# version_1.net
KiCad netlist of a schematic drawn in EAGLE
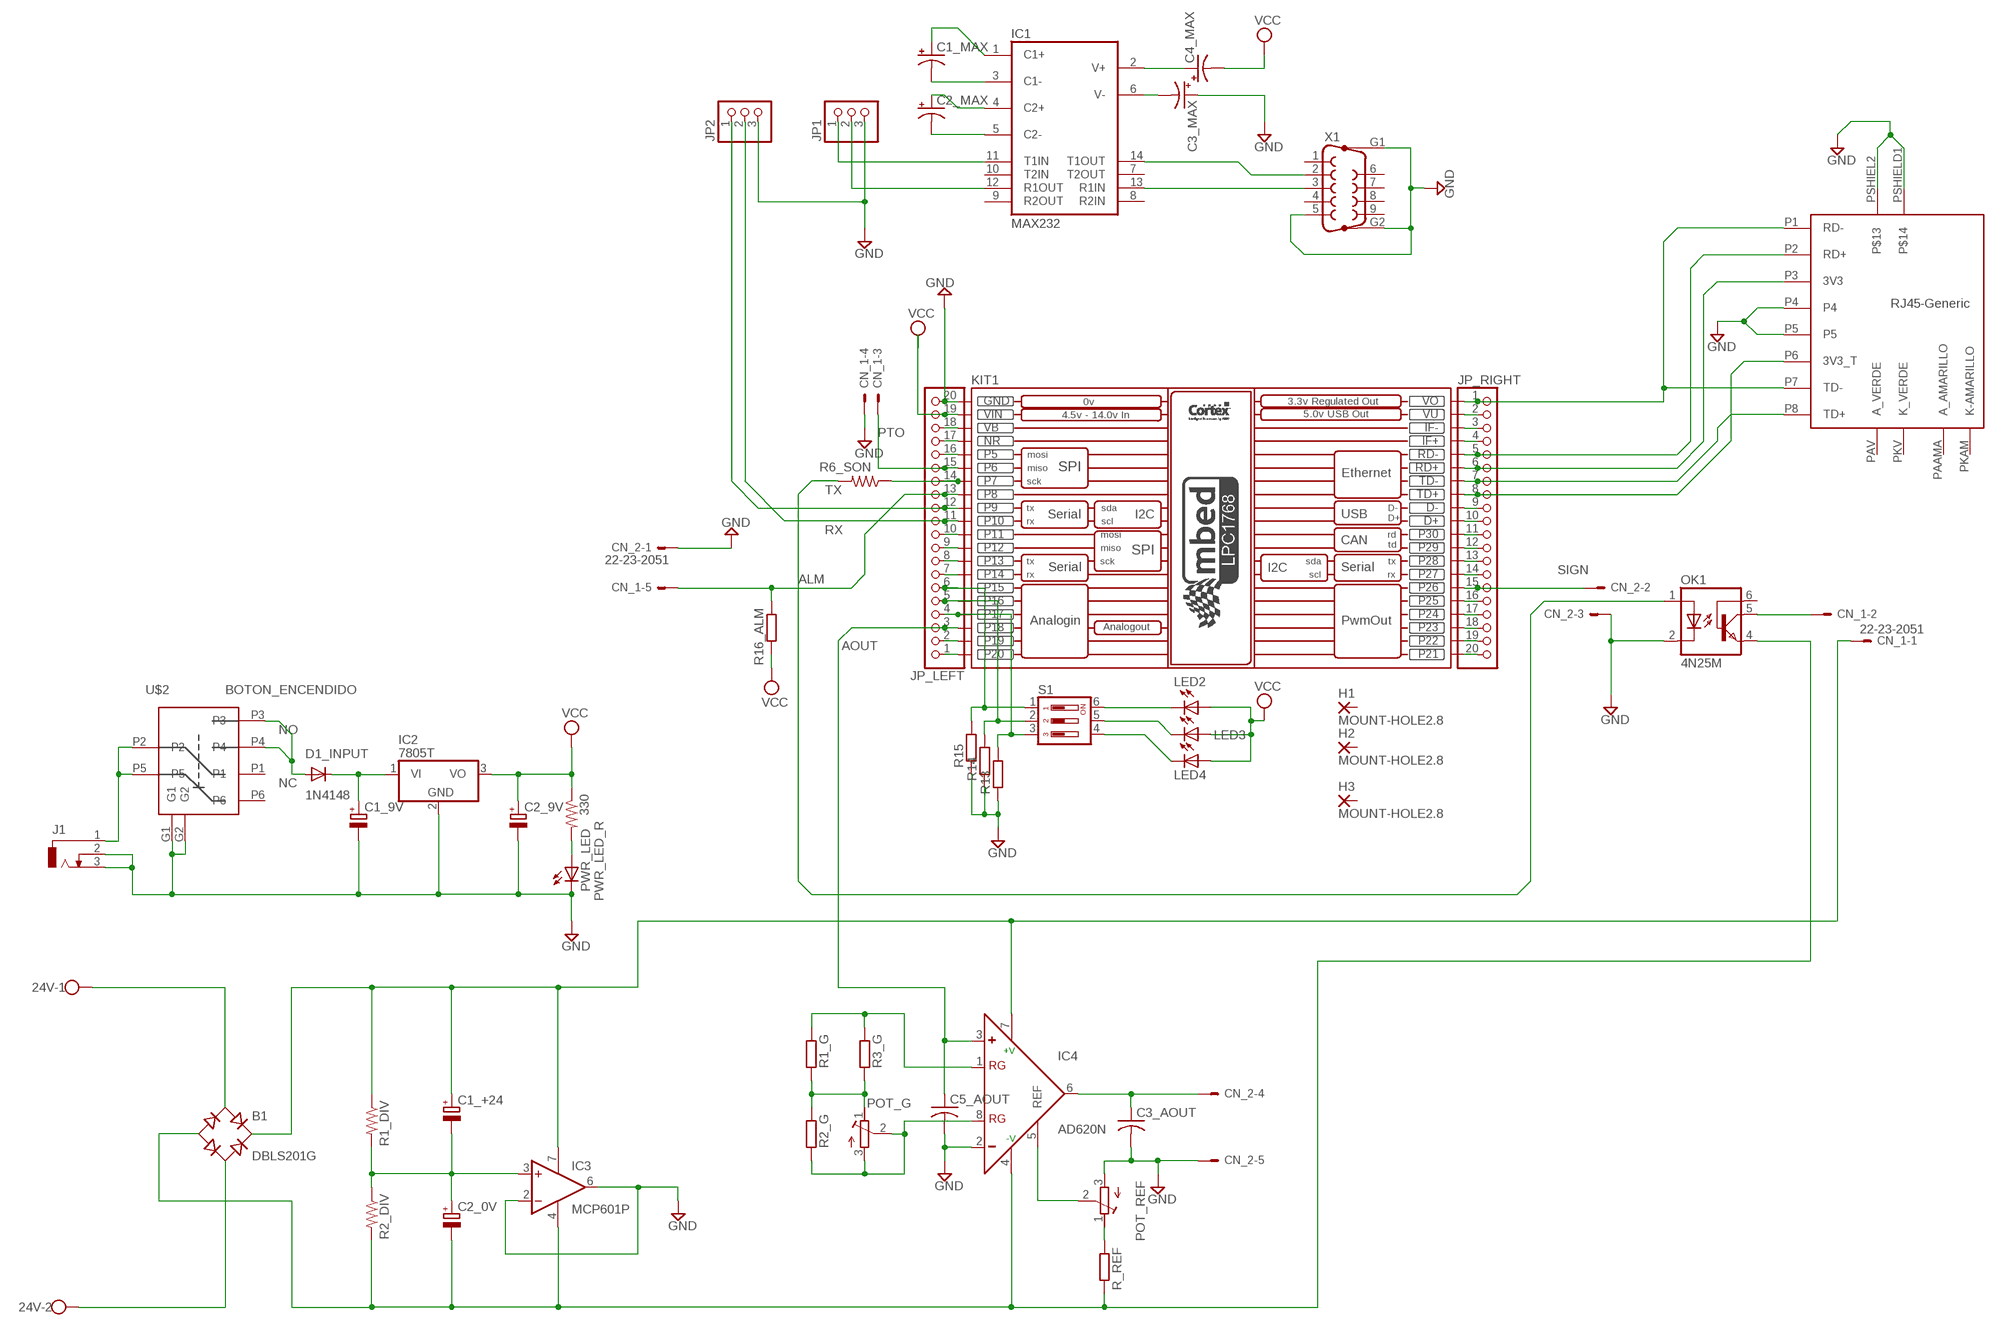
[diagram p0: schematic, sheet 1]

(export (version "E")
  (design (tool "Eeschema 10.0.6"))
  (components
    (comp (ref "24V")
      (value "W237-02P")
      (footprint "eagle-import:W237-132")
      (libsource (lib "eagle-import") (part "W237-02P"))
    )
    (comp (ref "B1")
      (value "DBLS201G")
      (footprint "eagle-import:DBS")
      (libsource (lib "eagle-import") (part "DB?GLS201"))
    )
    (comp (ref "C1_+24")
      (value "CPOL-EUTT5D7")
      (footprint "eagle-import:TT5D7")
      (libsource (lib "eagle-import") (part "CPOL-EUTT5D7"))
    )
    (comp (ref "C1_9V")
      (value "CPOL-EUTT5D7")
      (footprint "eagle-import:TT5D7")
      (libsource (lib "eagle-import") (part "CPOL-EUTT5D7"))
    )
    (comp (ref "C1_MAX")
      (value "CPOL-USE2,5-6E")
      (footprint "eagle-import:E2,5-6E")
      (libsource (lib "eagle-import") (part "CPOL-USE2,5-6E"))
    )
    (comp (ref "C2_0V")
      (value "CPOL-EUTT5D7")
      (footprint "eagle-import:TT5D7")
      (libsource (lib "eagle-import") (part "CPOL-EUTT5D7"))
    )
    (comp (ref "C2_9V")
      (value "CPOL-EUTT5D7")
      (footprint "eagle-import:TT5D7")
      (libsource (lib "eagle-import") (part "CPOL-EUTT5D7"))
    )
    (comp (ref "C2_MAX")
      (value "CPOL-USE2,5-6E")
      (footprint "eagle-import:E2,5-6E")
      (libsource (lib "eagle-import") (part "CPOL-USE2,5-6E"))
    )
    (comp (ref "C3_AOUT")
      (value "C-US025-024X044")
      (footprint "eagle-import:C025-024X044")
      (libsource (lib "eagle-import") (part "C-US025-024X044"))
    )
    (comp (ref "C3_MAX")
      (value "CPOL-USE2,5-6E")
      (footprint "eagle-import:E2,5-6E")
      (libsource (lib "eagle-import") (part "CPOL-USE2,5-6E"))
    )
    (comp (ref "C4_MAX")
      (value "CPOL-USE2,5-6E")
      (footprint "eagle-import:E2,5-6E")
      (libsource (lib "eagle-import") (part "CPOL-USE2,5-6E"))
    )
    (comp (ref "C5_AOUT")
      (value "C-US025-024X044")
      (footprint "eagle-import:C025-024X044")
      (libsource (lib "eagle-import") (part "C-US025-024X044"))
    )
    (comp (ref "CN_1")
      (value "22-23-2051")
      (footprint "eagle-import:22-23-2051")
      (libsource (lib "eagle-import") (part "22-23-2051"))
    )
    (comp (ref "CN_2")
      (value "22-23-2051")
      (footprint "eagle-import:22-23-2051")
      (libsource (lib "eagle-import") (part "22-23-2051"))
    )
    (comp (ref "D1_INPUT")
      (value "1N4148")
      (footprint "eagle-import:DO35-10")
      (libsource (lib "eagle-import") (part "1N4148DO35-10"))
    )
    (comp (ref "H1")
      (value "MOUNT-HOLE2.8")
      (footprint "eagle-import:2,54_0,8")
      (libsource (lib "eagle-import") (part "2,54/0,8"))
    )
    (comp (ref "H2")
      (value "MOUNT-HOLE2.8")
      (footprint "eagle-import:2,54_0,8")
      (libsource (lib "eagle-import") (part "2,54/0,8"))
    )
    (comp (ref "H3")
      (value "MOUNT-HOLE2.8")
      (footprint "eagle-import:2,54_0,8")
      (libsource (lib "eagle-import") (part "2,54/0,8"))
    )
    (comp (ref "IC1")
      (value "MAX232")
      (footprint "eagle-import:DIL16")
      (libsource (lib "eagle-import") (part "MAX232"))
    )
    (comp (ref "IC2")
      (value "7805T")
      (footprint "eagle-import:TO220H")
      (libsource (lib "eagle-import") (part "78T05"))
    )
    (comp (ref "IC3")
      (value "MCP601P")
      (footprint "eagle-import:DIL08")
      (libsource (lib "eagle-import") (part "MCP601P"))
    )
    (comp (ref "IC4")
      (value "AD620N")
      (footprint "eagle-import:DIL08")
      (libsource (lib "eagle-import") (part "AD620N"))
    )
    (comp (ref "J1")
      (value "DCJ0303")
      (footprint "eagle-import:DCJ0303")
      (libsource (lib "eagle-import") (part "DCJ0303"))
    )
    (comp (ref "JP1")
      (value "PINHD-1X3")
      (footprint "eagle-import:1X03")
      (libsource (lib "eagle-import") (part "PINHD-1X3"))
    )
    (comp (ref "JP2")
      (value "PINHD-1X3")
      (footprint "eagle-import:1X03")
      (libsource (lib "eagle-import") (part "PINHD-1X3"))
    )
    (comp (ref "JP_LEFT")
      (value "PINHD-1X20")
      (footprint "eagle-import:1X20")
      (libsource (lib "eagle-import") (part "PINHD-1X20"))
    )
    (comp (ref "JP_RIGHT")
      (value "PINHD-1X20")
      (footprint "eagle-import:1X20")
      (libsource (lib "eagle-import") (part "PINHD-1X20"))
    )
    (comp (ref "KIT1")
      (value "MBED_NXP_LPC1768")
      (footprint "eagle-import:MBED-KIT")
      (libsource (lib "eagle-import") (part "MBED_NXP_LPC1768"))
    )
    (comp (ref "LED2")
      (value "LED3MM")
      (footprint "eagle-import:LED3MM")
      (libsource (lib "eagle-import") (part "LED3MM"))
    )
    (comp (ref "LED3")
      (value "LED3MM")
      (footprint "eagle-import:LED3MM")
      (libsource (lib "eagle-import") (part "LED3MM"))
    )
    (comp (ref "LED4")
      (value "LED3MM")
      (footprint "eagle-import:LED3MM")
      (libsource (lib "eagle-import") (part "LED3MM"))
    )
    (comp (ref "OK1")
      (value "4N25M")
      (footprint "eagle-import:DIL06")
      (libsource (lib "eagle-import") (part "4N?M25"))
    )
    (comp (ref "POT_G")
      (value "R-TRIMMT93XB")
      (footprint "eagle-import:RTRIMT93XB")
      (libsource (lib "eagle-import") (part "R-TRIMMT93XB"))
    )
    (comp (ref "POT_REF")
      (value "R-TRIMMT93XB")
      (footprint "eagle-import:RTRIMT93XB")
      (libsource (lib "eagle-import") (part "R-TRIMMT93XB"))
    )
    (comp (ref "PWR_LED")
      (value "LED3MM")
      (footprint "eagle-import:LED3MM")
      (libsource (lib "eagle-import") (part "LED3MM"))
    )
    (comp (ref "PWR_LED_R")
      (value "330")
      (footprint "eagle-import:0207_15")
      (libsource (lib "eagle-import") (part "R-US_0207/15"))
    )
    (comp (ref "R1_DIV")
      (value "R-US_0207/10")
      (footprint "eagle-import:0207_10")
      (libsource (lib "eagle-import") (part "resistor_R-US_0207/10"))
    )
    (comp (ref "R1_G")
      (value "R-EU_0207/2V")
      (footprint "eagle-import:0207_2V")
      (libsource (lib "eagle-import") (part "R-EU_0207/2V"))
    )
    (comp (ref "R2_DIV")
      (value "R-US_0207/10")
      (footprint "eagle-import:0207_10")
      (libsource (lib "eagle-import") (part "resistor_R-US_0207/10"))
    )
    (comp (ref "R2_G")
      (value "R-EU_0207/2V")
      (footprint "eagle-import:0207_2V")
      (libsource (lib "eagle-import") (part "R-EU_0207/2V"))
    )
    (comp (ref "R3_G")
      (value "R-EU_0207/2V")
      (footprint "eagle-import:0207_2V")
      (libsource (lib "eagle-import") (part "R-EU_0207/2V"))
    )
    (comp (ref "R6_SON")
      (value "R-US_0207/7")
      (footprint "eagle-import:0207_7")
      (libsource (lib "eagle-import") (part "R-US_0207/7"))
    )
    (comp (ref "R13")
      (value "R-EU_0207/15")
      (footprint "eagle-import:0207_15")
      (libsource (lib "eagle-import") (part "R-EU_0207/15"))
    )
    (comp (ref "R14")
      (value "R-EU_0207/15")
      (footprint "eagle-import:0207_15")
      (libsource (lib "eagle-import") (part "R-EU_0207/15"))
    )
    (comp (ref "R15")
      (value "R-EU_0207/15")
      (footprint "eagle-import:0207_15")
      (libsource (lib "eagle-import") (part "R-EU_0207/15"))
    )
    (comp (ref "R16_ALM")
      (value "R-EU_0207/12")
      (footprint "eagle-import:0207_12")
      (libsource (lib "eagle-import") (part "R-EU_0207/12"))
    )
    (comp (ref "R_REF")
      (value "R-EU_0207/2V")
      (footprint "eagle-import:0207_2V")
      (libsource (lib "eagle-import") (part "R-EU_0207/2V"))
    )
    (comp (ref "S1")
      (value "DIP03YL")
      (footprint "eagle-import:DIP03YL")
      (libsource (lib "eagle-import") (part "DIP03YL"))
    )
    (comp (ref "U$1")
      (value "RJ-45-GENERIC")
      (footprint "eagle-import:RJ45-GENERIC")
      (libsource (lib "eagle-import") (part "RJ-45-GENERIC"))
    )
    (comp (ref "U$2")
      (value "BOTON_ENCENDIDO")
      (footprint "eagle-import:BOTON_ENCNEDIDO")
      (libsource (lib "eagle-import") (part "BOTON_ENCENDIDO"))
    )
    (comp (ref "X1")
      (value "F09HP")
      (footprint "eagle-import:F09HP")
      (libsource (lib "eagle-import") (part "F09HP"))
    )
  )
  (nets
    (net (code "1") (name "/ALM") (class "Default")
      (node (ref "CN_1") (pin "5") (pinfunction "S_5") (pintype "passive"))
      (node (ref "JP_LEFT") (pin "13") (pinfunction "13_13") (pintype "passive"))
      (node (ref "KIT1") (pin "P$8") (pinfunction "P8_P$8") (pintype "bidirectional"))
      (node (ref "R16_ALM") (pin "1") (pinfunction "1_1") (pintype "passive"))
    )
    (net (code "2") (name "/AOUT") (class "Default")
      (node (ref "C5_AOUT") (pin "1") (pinfunction "1_1") (pintype "passive"))
      (node (ref "IC4") (pin "3") (pinfunction "+_3") (pintype "input"))
      (node (ref "JP_LEFT") (pin "3") (pinfunction "3_3") (pintype "passive"))
      (node (ref "KIT1") (pin "P$18") (pinfunction "P18_P$18") (pintype "bidirectional"))
    )
    (net (code "3") (name "/PTO") (class "Default")
      (node (ref "CN_1") (pin "3") (pinfunction "S_3") (pintype "passive"))
      (node (ref "JP_LEFT") (pin "15") (pinfunction "15_15") (pintype "passive"))
      (node (ref "KIT1") (pin "P$6") (pinfunction "P6_P$6") (pintype "bidirectional"))
    )
    (net (code "4") (name "/RX") (class "Default")
      (node (ref "JP2") (pin "2") (pinfunction "2_2") (pintype "passive"))
      (node (ref "JP_LEFT") (pin "11") (pinfunction "11_11") (pintype "passive"))
      (node (ref "KIT1") (pin "P$10") (pinfunction "P10_P$10") (pintype "bidirectional"))
    )
    (net (code "5") (name "/SIGN") (class "Default")
      (node (ref "CN_2") (pin "2") (pinfunction "S_2") (pintype "passive"))
      (node (ref "JP_RIGHT") (pin "15") (pinfunction "15_15") (pintype "passive"))
      (node (ref "KIT1") (pin "P$26") (pinfunction "P26_P$26") (pintype "bidirectional"))
    )
    (net (code "6") (name "/TX") (class "Default")
      (node (ref "JP2") (pin "1") (pinfunction "1_1") (pintype "passive"))
      (node (ref "JP_LEFT") (pin "12") (pinfunction "12_12") (pintype "passive"))
      (node (ref "KIT1") (pin "P$9") (pinfunction "P9_P$9") (pintype "bidirectional"))
    )
    (net (code "7") (name "GND") (class "Default")
      (node (ref "C1_9V") (pin "-") (pinfunction "-_-") (pintype "passive"))
      (node (ref "C2_9V") (pin "-") (pinfunction "-_-") (pintype "passive"))
      (node (ref "C3_AOUT") (pin "2") (pinfunction "2_2") (pintype "passive"))
      (node (ref "C3_MAX") (pin "+") (pinfunction "+_+") (pintype "passive"))
      (node (ref "C5_AOUT") (pin "2") (pinfunction "2_2") (pintype "passive"))
      (node (ref "CN_1") (pin "4") (pinfunction "S_4") (pintype "passive"))
      (node (ref "CN_2") (pin "1") (pinfunction "S_1") (pintype "passive"))
      (node (ref "CN_2") (pin "3") (pinfunction "S_3") (pintype "passive"))
      (node (ref "CN_2") (pin "5") (pinfunction "S_5") (pintype "passive"))
      (node (ref "IC2") (pin "2") (pinfunction "GND_2") (pintype "passive"))
      (node (ref "IC3") (pin "2") (pinfunction "-IN_2") (pintype "input"))
      (node (ref "IC3") (pin "6") (pinfunction "OUT_6") (pintype "output"))
      (node (ref "IC4") (pin "2") (pinfunction "-_2") (pintype "input"))
      (node (ref "J1") (pin "2") (pinfunction "2_2") (pintype "passive"))
      (node (ref "J1") (pin "3") (pinfunction "3_3") (pintype "passive"))
      (node (ref "JP1") (pin "3") (pinfunction "3_3") (pintype "passive"))
      (node (ref "JP2") (pin "3") (pinfunction "3_3") (pintype "passive"))
      (node (ref "JP_LEFT") (pin "20") (pinfunction "20_20") (pintype "passive"))
      (node (ref "KIT1") (pin "GND") (pinfunction "GND_GND") (pintype "power_in"))
      (node (ref "OK1") (pin "2") (pinfunction "C_2") (pintype "passive"))
      (node (ref "POT_REF") (pin "3") (pinfunction "E_3") (pintype "passive"))
      (node (ref "PWR_LED") (pin "K") (pinfunction "C_K") (pintype "passive"))
      (node (ref "R13") (pin "1") (pinfunction "1_1") (pintype "passive"))
      (node (ref "R14") (pin "1") (pinfunction "1_1") (pintype "passive"))
      (node (ref "R15") (pin "1") (pinfunction "1_1") (pintype "passive"))
      (node (ref "U$1") (pin "P4") (pinfunction "P4_P4") (pintype "bidirectional"))
      (node (ref "U$1") (pin "P5") (pinfunction "P5_P5") (pintype "bidirectional"))
      (node (ref "U$1") (pin "PSHIEL2") (pinfunction "P$13_PSHIEL2") (pintype "bidirectional"))
      (node (ref "U$1") (pin "PSHIELD1") (pinfunction "P$14_PSHIELD1") (pintype "bidirectional"))
      (node (ref "U$2") (pin "G1") (pinfunction "G1_G1") (pintype "bidirectional"))
      (node (ref "U$2") (pin "G2") (pinfunction "G2_G2") (pintype "bidirectional"))
      (node (ref "X1") (pin "5") (pinfunction "5_5") (pintype "passive"))
      (node (ref "X1") (pin "G1") (pinfunction "G1_G1") (pintype "passive"))
      (node (ref "X1") (pin "G2") (pinfunction "G2_G2") (pintype "passive"))
    )
    (net (code "8") (name "Net-(24VA-KL)") (class "Default")
      (node (ref "24V") (pin "1") (pinfunction "KL_1") (pintype "passive"))
      (node (ref "B1") (pin "AC1") (pinfunction "AC1_AC1") (pintype "passive"))
    )
    (net (code "9") (name "Net-(24VB-KL)") (class "Default")
      (node (ref "24V") (pin "2") (pinfunction "KL_2") (pintype "passive"))
      (node (ref "B1") (pin "AC2") (pinfunction "AC2_AC2") (pintype "passive"))
    )
    (net (code "10") (name "Net-(CN_1A-S)") (class "Default")
      (node (ref "B1") (pin "+") (pinfunction "+_+") (pintype "passive"))
      (node (ref "C1_+24") (pin "+") (pinfunction "+_+") (pintype "passive"))
      (node (ref "CN_1") (pin "1") (pinfunction "S_1") (pintype "passive"))
      (node (ref "IC3") (pin "7") (pinfunction "V+_7") (pintype "power_in"))
      (node (ref "IC4") (pin "7") (pinfunction "+V_7") (pintype "power_in"))
      (node (ref "R1_DIV") (pin "1") (pinfunction "1_1") (pintype "passive"))
    )
    (net (code "11") (name "Net-(CN_1B-S)") (class "Default")
      (node (ref "CN_1") (pin "2") (pinfunction "S_2") (pintype "passive"))
      (node (ref "OK1") (pin "5") (pinfunction "COL_5") (pintype "passive"))
    )
    (net (code "12") (name "Net-(CN_2D-S)") (class "Default")
      (node (ref "C3_AOUT") (pin "1") (pinfunction "1_1") (pintype "passive"))
      (node (ref "CN_2") (pin "4") (pinfunction "S_4") (pintype "passive"))
      (node (ref "IC4") (pin "6") (pinfunction "OUT_6") (pintype "output"))
    )
    (net (code "13") (name "Net-(D1_INPUT-PadA)") (class "Default")
      (node (ref "D1_INPUT") (pin "A") (pinfunction "A_A") (pintype "passive"))
      (node (ref "U$2") (pin "P3") (pinfunction "P3_P3") (pintype "bidirectional"))
      (node (ref "U$2") (pin "P4") (pinfunction "P4_P4") (pintype "bidirectional"))
    )
    (net (code "14") (name "Net-(IC1A-C1+)") (class "Default")
      (node (ref "C1_MAX") (pin "+") (pinfunction "+_+") (pintype "passive"))
      (node (ref "IC1") (pin "1") (pinfunction "C1+_1") (pintype "bidirectional"))
    )
    (net (code "15") (name "Net-(IC1A-C1-)") (class "Default")
      (node (ref "C1_MAX") (pin "-") (pinfunction "-_-") (pintype "passive"))
      (node (ref "IC1") (pin "3") (pinfunction "C1-_3") (pintype "bidirectional"))
    )
    (net (code "16") (name "Net-(IC1A-C2+)") (class "Default")
      (node (ref "C2_MAX") (pin "+") (pinfunction "+_+") (pintype "passive"))
      (node (ref "IC1") (pin "4") (pinfunction "C2+_4") (pintype "bidirectional"))
    )
    (net (code "17") (name "Net-(IC1A-C2-)") (class "Default")
      (node (ref "C2_MAX") (pin "-") (pinfunction "-_-") (pintype "passive"))
      (node (ref "IC1") (pin "5") (pinfunction "C2-_5") (pintype "bidirectional"))
    )
    (net (code "18") (name "Net-(IC1A-R1IN)") (class "Default")
      (node (ref "IC1") (pin "13") (pinfunction "R1IN_13") (pintype "input"))
      (node (ref "X1") (pin "3") (pinfunction "3_3") (pintype "passive"))
    )
    (net (code "19") (name "Net-(IC1A-R1OUT)") (class "Default")
      (node (ref "IC1") (pin "12") (pinfunction "R1OUT_12") (pintype "output"))
      (node (ref "JP1") (pin "2") (pinfunction "2_2") (pintype "passive"))
    )
    (net (code "20") (name "Net-(IC1A-T1IN)") (class "Default")
      (node (ref "IC1") (pin "11") (pinfunction "T1IN_11") (pintype "input"))
      (node (ref "JP1") (pin "1") (pinfunction "1_1") (pintype "passive"))
    )
    (net (code "21") (name "Net-(IC1A-T1OUT)") (class "Default")
      (node (ref "IC1") (pin "14") (pinfunction "T1OUT_14") (pintype "output"))
      (node (ref "X1") (pin "2") (pinfunction "2_2") (pintype "passive"))
    )
    (net (code "22") (name "Net-(IC1A-V+)") (class "Default")
      (node (ref "C4_MAX") (pin "+") (pinfunction "+_+") (pintype "passive"))
      (node (ref "IC1") (pin "2") (pinfunction "V+_2") (pintype "bidirectional"))
    )
    (net (code "23") (name "Net-(IC1A-V-)") (class "Default")
      (node (ref "C3_MAX") (pin "-") (pinfunction "-_-") (pintype "passive"))
      (node (ref "IC1") (pin "6") (pinfunction "V-_6") (pintype "bidirectional"))
    )
    (net (code "24") (name "Net-(IC2-VI)") (class "Default")
      (node (ref "C1_9V") (pin "+") (pinfunction "+_+") (pintype "passive"))
      (node (ref "D1_INPUT") (pin "C") (pinfunction "C_C") (pintype "passive"))
      (node (ref "IC2") (pin "1") (pinfunction "VI_1") (pintype "input"))
    )
    (net (code "25") (name "Net-(IC3-+IN)") (class "Default")
      (node (ref "C1_+24") (pin "-") (pinfunction "-_-") (pintype "passive"))
      (node (ref "C2_0V") (pin "+") (pinfunction "+_+") (pintype "passive"))
      (node (ref "IC3") (pin "3") (pinfunction "+IN_3") (pintype "input"))
      (node (ref "R1_DIV") (pin "2") (pinfunction "2_2") (pintype "passive"))
      (node (ref "R2_DIV") (pin "1") (pinfunction "1_1") (pintype "passive"))
    )
    (net (code "26") (name "Net-(IC3-V-)") (class "Default")
      (node (ref "B1") (pin "-") (pinfunction "-_-") (pintype "passive"))
      (node (ref "C2_0V") (pin "-") (pinfunction "-_-") (pintype "passive"))
      (node (ref "IC3") (pin "4") (pinfunction "V-_4") (pintype "power_in"))
      (node (ref "IC4") (pin "4") (pinfunction "-V_4") (pintype "power_in"))
      (node (ref "OK1") (pin "4") (pinfunction "EMI_4") (pintype "passive"))
      (node (ref "R2_DIV") (pin "2") (pinfunction "2_2") (pintype "passive"))
      (node (ref "R_REF") (pin "2") (pinfunction "2_2") (pintype "passive"))
    )
    (net (code "27") (name "Net-(IC4-REF)") (class "Default")
      (node (ref "IC4") (pin "5") (pinfunction "REF_5") (pintype "passive"))
      (node (ref "POT_REF") (pin "2") (pinfunction "S_2") (pintype "passive"))
    )
    (net (code "28") (name "Net-(IC4-RG-Pad1)") (class "Default")
      (node (ref "IC4") (pin "1") (pinfunction "RG_1") (pintype "passive"))
      (node (ref "R1_G") (pin "1") (pinfunction "1_1") (pintype "passive"))
      (node (ref "R3_G") (pin "1") (pinfunction "1_1") (pintype "passive"))
    )
    (net (code "29") (name "Net-(J1-Pad1)") (class "Default")
      (node (ref "J1") (pin "1") (pinfunction "1_1") (pintype "passive"))
      (node (ref "U$2") (pin "P2") (pinfunction "P2_P2") (pintype "bidirectional"))
      (node (ref "U$2") (pin "P5") (pinfunction "P5_P5") (pintype "bidirectional"))
    )
    (net (code "30") (name "Net-(JP_LEFT-Pad17)") (class "Default")
      (node (ref "JP_LEFT") (pin "17") (pinfunction "17_17") (pintype "passive"))
      (node (ref "KIT1") (pin "NR") (pinfunction "NR_NR") (pintype "power_in"))
    )
    (net (code "31") (name "Net-(JP_LEFT-Pad18)") (class "Default")
      (node (ref "JP_LEFT") (pin "18") (pinfunction "18_18") (pintype "passive"))
      (node (ref "KIT1") (pin "VB") (pinfunction "VB_VB") (pintype "power_in"))
    )
    (net (code "32") (name "Net-(JP_RIGHT-Pad2)") (class "Default")
      (node (ref "JP_RIGHT") (pin "2") (pinfunction "2_2") (pintype "passive"))
      (node (ref "KIT1") (pin "VU") (pinfunction "VU_VU") (pintype "power_in"))
    )
    (net (code "33") (name "Net-(JP_RIGHT-Pad3)") (class "Default")
      (node (ref "JP_RIGHT") (pin "3") (pinfunction "3_3") (pintype "passive"))
      (node (ref "KIT1") (pin "IF-") (pinfunction "IF-_IF-") (pintype "bidirectional"))
    )
    (net (code "34") (name "Net-(JP_RIGHT-Pad4)") (class "Default")
      (node (ref "JP_RIGHT") (pin "4") (pinfunction "4_4") (pintype "passive"))
      (node (ref "KIT1") (pin "IF+") (pinfunction "IF+_IF+") (pintype "bidirectional"))
    )
    (net (code "35") (name "Net-(JP_RIGHT-Pad9)") (class "Default")
      (node (ref "JP_RIGHT") (pin "9") (pinfunction "9_9") (pintype "passive"))
      (node (ref "KIT1") (pin "D-") (pinfunction "D-_D-") (pintype "bidirectional"))
    )
    (net (code "36") (name "Net-(JP_RIGHT-Pad10)") (class "Default")
      (node (ref "JP_RIGHT") (pin "10") (pinfunction "10_10") (pintype "passive"))
      (node (ref "KIT1") (pin "D+") (pinfunction "D+_D+") (pintype "bidirectional"))
    )
    (net (code "37") (name "Net-(KIT1-P5)") (class "Default")
      (node (ref "JP_LEFT") (pin "16") (pinfunction "16_16") (pintype "passive"))
      (node (ref "KIT1") (pin "P$5") (pinfunction "P5_P$5") (pintype "bidirectional"))
    )
    (net (code "38") (name "Net-(KIT1-P7)") (class "Default")
      (node (ref "JP_LEFT") (pin "14") (pinfunction "14_14") (pintype "passive"))
      (node (ref "KIT1") (pin "P$7") (pinfunction "P7_P$7") (pintype "bidirectional"))
      (node (ref "R6_SON") (pin "1") (pinfunction "1_1") (pintype "passive"))
    )
    (net (code "39") (name "Net-(KIT1-P11)") (class "Default")
      (node (ref "JP_LEFT") (pin "10") (pinfunction "10_10") (pintype "passive"))
      (node (ref "KIT1") (pin "P$11") (pinfunction "P11_P$11") (pintype "bidirectional"))
    )
    (net (code "40") (name "Net-(KIT1-P12)") (class "Default")
      (node (ref "JP_LEFT") (pin "9") (pinfunction "9_9") (pintype "passive"))
      (node (ref "KIT1") (pin "P$12") (pinfunction "P12_P$12") (pintype "bidirectional"))
    )
    (net (code "41") (name "Net-(KIT1-P13)") (class "Default")
      (node (ref "JP_LEFT") (pin "8") (pinfunction "8_8") (pintype "passive"))
      (node (ref "KIT1") (pin "P$13") (pinfunction "P13_P$13") (pintype "bidirectional"))
    )
    (net (code "42") (name "Net-(KIT1-P14)") (class "Default")
      (node (ref "JP_LEFT") (pin "7") (pinfunction "7_7") (pintype "passive"))
      (node (ref "KIT1") (pin "P$14") (pinfunction "P14_P$14") (pintype "bidirectional"))
    )
    (net (code "43") (name "Net-(KIT1-P15)") (class "Default")
      (node (ref "JP_LEFT") (pin "6") (pinfunction "6_6") (pintype "passive"))
      (node (ref "KIT1") (pin "P$15") (pinfunction "P15_P$15") (pintype "bidirectional"))
      (node (ref "R15") (pin "2") (pinfunction "2_2") (pintype "passive"))
      (node (ref "S1") (pin "1") (pinfunction "1_1") (pintype "passive"))
    )
    (net (code "44") (name "Net-(KIT1-P16)") (class "Default")
      (node (ref "JP_LEFT") (pin "5") (pinfunction "5_5") (pintype "passive"))
      (node (ref "KIT1") (pin "P$16") (pinfunction "P16_P$16") (pintype "bidirectional"))
      (node (ref "R14") (pin "2") (pinfunction "2_2") (pintype "passive"))
      (node (ref "S1") (pin "2") (pinfunction "2_2") (pintype "passive"))
    )
    (net (code "45") (name "Net-(KIT1-P17)") (class "Default")
      (node (ref "JP_LEFT") (pin "4") (pinfunction "4_4") (pintype "passive"))
      (node (ref "KIT1") (pin "P$17") (pinfunction "P17_P$17") (pintype "bidirectional"))
      (node (ref "R13") (pin "2") (pinfunction "2_2") (pintype "passive"))
      (node (ref "S1") (pin "3") (pinfunction "3_3") (pintype "passive"))
    )
    (net (code "46") (name "Net-(KIT1-P19)") (class "Default")
      (node (ref "JP_LEFT") (pin "2") (pinfunction "2_2") (pintype "passive"))
      (node (ref "KIT1") (pin "P$19") (pinfunction "P19_P$19") (pintype "bidirectional"))
    )
    (net (code "47") (name "Net-(KIT1-P20)") (class "Default")
      (node (ref "JP_LEFT") (pin "1") (pinfunction "1_1") (pintype "passive"))
      (node (ref "KIT1") (pin "P$20") (pinfunction "P20_P$20") (pintype "bidirectional"))
    )
    (net (code "48") (name "Net-(KIT1-P21)") (class "Default")
      (node (ref "JP_RIGHT") (pin "20") (pinfunction "20_20") (pintype "passive"))
      (node (ref "KIT1") (pin "P$21") (pinfunction "P21_P$21") (pintype "bidirectional"))
    )
    (net (code "49") (name "Net-(KIT1-P22)") (class "Default")
      (node (ref "JP_RIGHT") (pin "19") (pinfunction "19_19") (pintype "passive"))
      (node (ref "KIT1") (pin "P$22") (pinfunction "P22_P$22") (pintype "bidirectional"))
    )
    (net (code "50") (name "Net-(KIT1-P23)") (class "Default")
      (node (ref "JP_RIGHT") (pin "18") (pinfunction "18_18") (pintype "passive"))
      (node (ref "KIT1") (pin "P$23") (pinfunction "P23_P$23") (pintype "bidirectional"))
    )
    (net (code "51") (name "Net-(KIT1-P24)") (class "Default")
      (node (ref "JP_RIGHT") (pin "17") (pinfunction "17_17") (pintype "passive"))
      (node (ref "KIT1") (pin "P$24") (pinfunction "P24_P$24") (pintype "bidirectional"))
    )
    (net (code "52") (name "Net-(KIT1-P25)") (class "Default")
      (node (ref "JP_RIGHT") (pin "16") (pinfunction "16_16") (pintype "passive"))
      (node (ref "KIT1") (pin "P$25") (pinfunction "P25_P$25") (pintype "bidirectional"))
    )
    (net (code "53") (name "Net-(KIT1-P27)") (class "Default")
      (node (ref "JP_RIGHT") (pin "14") (pinfunction "14_14") (pintype "passive"))
      (node (ref "KIT1") (pin "P$27") (pinfunction "P27_P$27") (pintype "bidirectional"))
    )
    (net (code "54") (name "Net-(KIT1-P28)") (class "Default")
      (node (ref "JP_RIGHT") (pin "13") (pinfunction "13_13") (pintype "passive"))
      (node (ref "KIT1") (pin "P$28") (pinfunction "P28_P$28") (pintype "bidirectional"))
    )
    (net (code "55") (name "Net-(KIT1-P29)") (class "Default")
      (node (ref "JP_RIGHT") (pin "12") (pinfunction "12_12") (pintype "passive"))
      (node (ref "KIT1") (pin "P$29") (pinfunction "P29_P$29") (pintype "bidirectional"))
    )
    (net (code "56") (name "Net-(KIT1-P30)") (class "Default")
      (node (ref "JP_RIGHT") (pin "11") (pinfunction "11_11") (pintype "passive"))
      (node (ref "KIT1") (pin "P$30") (pinfunction "P30_P$30") (pintype "bidirectional"))
    )
    (net (code "57") (name "Net-(KIT1-VO)") (class "Default")
      (node (ref "JP_RIGHT") (pin "1") (pinfunction "1_1") (pintype "passive"))
      (node (ref "KIT1") (pin "VOUT") (pinfunction "VO_VOUT") (pintype "power_in"))
      (node (ref "U$1") (pin "P1") (pinfunction "RD-_P1") (pintype "bidirectional"))
      (node (ref "U$1") (pin "P7") (pinfunction "TD-_P7") (pintype "bidirectional"))
    )
    (net (code "58") (name "Net-(LED2-C)") (class "Default")
      (node (ref "LED2") (pin "K") (pinfunction "C_K") (pintype "passive"))
      (node (ref "S1") (pin "6") (pinfunction "6_6") (pintype "passive"))
    )
    (net (code "59") (name "Net-(LED3-C)") (class "Default")
      (node (ref "LED3") (pin "K") (pinfunction "C_K") (pintype "passive"))
      (node (ref "S1") (pin "5") (pinfunction "5_5") (pintype "passive"))
    )
    (net (code "60") (name "Net-(LED4-C)") (class "Default")
      (node (ref "LED4") (pin "K") (pinfunction "C_K") (pintype "passive"))
      (node (ref "S1") (pin "4") (pinfunction "4_4") (pintype "passive"))
    )
    (net (code "61") (name "Net-(OK1-A)") (class "Default")
      (node (ref "OK1") (pin "1") (pinfunction "A_1") (pintype "passive"))
      (node (ref "R6_SON") (pin "2") (pinfunction "2_2") (pintype "passive"))
    )
    (net (code "62") (name "Net-(POT_G-A)") (class "Default")
      (node (ref "POT_G") (pin "1") (pinfunction "A_1") (pintype "passive"))
      (node (ref "R1_G") (pin "2") (pinfunction "2_2") (pintype "passive"))
      (node (ref "R2_G") (pin "1") (pinfunction "1_1") (pintype "passive"))
      (node (ref "R3_G") (pin "2") (pinfunction "2_2") (pintype "passive"))
    )
    (net (code "63") (name "Net-(POT_G-E)") (class "Default")
      (node (ref "IC4") (pin "8") (pinfunction "RG_8") (pintype "passive"))
      (node (ref "POT_G") (pin "2") (pinfunction "S_2") (pintype "passive"))
      (node (ref "POT_G") (pin "3") (pinfunction "E_3") (pintype "passive"))
      (node (ref "R2_G") (pin "2") (pinfunction "2_2") (pintype "passive"))
    )
    (net (code "64") (name "Net-(POT_REF-A)") (class "Default")
      (node (ref "POT_REF") (pin "1") (pinfunction "A_1") (pintype "passive"))
      (node (ref "R_REF") (pin "1") (pinfunction "1_1") (pintype "passive"))
    )
    (net (code "65") (name "Net-(PWR_LED-PadA)") (class "Default")
      (node (ref "PWR_LED") (pin "A") (pinfunction "A_A") (pintype "passive"))
      (node (ref "PWR_LED_R") (pin "2") (pinfunction "2_2") (pintype "passive"))
    )
    (net (code "66") (name "Net-(U$1-3V3)") (class "Default")
      (node (ref "JP_RIGHT") (pin "6") (pinfunction "6_6") (pintype "passive"))
      (node (ref "KIT1") (pin "RD+") (pinfunction "RD+_RD+") (pintype "bidirectional"))
      (node (ref "U$1") (pin "P3") (pinfunction "3V3_P3") (pintype "bidirectional"))
    )
    (net (code "67") (name "Net-(U$1-3V3_T)") (class "Default")
      (node (ref "JP_RIGHT") (pin "8") (pinfunction "8_8") (pintype "passive"))
      (node (ref "KIT1") (pin "TD+") (pinfunction "TD+_TD+") (pintype "bidirectional"))
      (node (ref "U$1") (pin "P6") (pinfunction "3V3_T_P6") (pintype "bidirectional"))
    )
    (net (code "68") (name "Net-(U$1-RD+)") (class "Default")
      (node (ref "JP_RIGHT") (pin "5") (pinfunction "5_5") (pintype "passive"))
      (node (ref "KIT1") (pin "RD-") (pinfunction "RD-_RD-") (pintype "bidirectional"))
      (node (ref "U$1") (pin "P2") (pinfunction "RD+_P2") (pintype "bidirectional"))
    )
    (net (code "69") (name "Net-(U$1-TD+)") (class "Default")
      (node (ref "JP_RIGHT") (pin "7") (pinfunction "7_7") (pintype "passive"))
      (node (ref "KIT1") (pin "TD-") (pinfunction "TD-_TD-") (pintype "bidirectional"))
      (node (ref "U$1") (pin "P8") (pinfunction "TD+_P8") (pintype "bidirectional"))
    )
    (net (code "70") (name "VCC") (class "Default")
      (node (ref "C2_9V") (pin "+") (pinfunction "+_+") (pintype "passive"))
      (node (ref "C4_MAX") (pin "-") (pinfunction "-_-") (pintype "passive"))
      (node (ref "IC2") (pin "3") (pinfunction "VO_3") (pintype "passive"))
      (node (ref "JP_LEFT") (pin "19") (pinfunction "19_19") (pintype "passive"))
      (node (ref "KIT1") (pin "VIN") (pinfunction "VIN_VIN") (pintype "power_in"))
      (node (ref "LED2") (pin "A") (pinfunction "A_A") (pintype "passive"))
      (node (ref "LED3") (pin "A") (pinfunction "A_A") (pintype "passive"))
      (node (ref "LED4") (pin "A") (pinfunction "A_A") (pintype "passive"))
      (node (ref "PWR_LED_R") (pin "1") (pinfunction "1_1") (pintype "passive"))
      (node (ref "R16_ALM") (pin "2") (pinfunction "2_2") (pintype "passive"))
    )
    (net (code "71") (name "unconnected-(H1-P-Pad1)") (class "Default")
      (node (ref "H1") (pin "1") (pinfunction "P_1") (pintype "passive"))
    )
    (net (code "72") (name "unconnected-(H2-P-Pad1)") (class "Default")
      (node (ref "H2") (pin "1") (pinfunction "P_1") (pintype "passive"))
    )
    (net (code "73") (name "unconnected-(H3-P-Pad1)") (class "Default")
      (node (ref "H3") (pin "1") (pinfunction "P_1") (pintype "passive"))
    )
    (net (code "74") (name "unconnected-(IC1A-R2IN-Pad8)") (class "Default")
      (node (ref "IC1") (pin "8") (pinfunction "R2IN_8") (pintype "input"))
    )
    (net (code "75") (name "unconnected-(IC1A-R2OUT-Pad9)") (class "Default")
      (node (ref "IC1") (pin "9") (pinfunction "R2OUT_9") (pintype "output"))
    )
    (net (code "76") (name "unconnected-(IC1A-T2IN-Pad10)") (class "Default")
      (node (ref "IC1") (pin "10") (pinfunction "T2IN_10") (pintype "input"))
    )
    (net (code "77") (name "unconnected-(IC1A-T2OUT-Pad7)") (class "Default")
      (node (ref "IC1") (pin "7") (pinfunction "T2OUT_7") (pintype "output"))
    )
    (net (code "78") (name "unconnected-(OK1-BAS-Pad6)") (class "Default")
      (node (ref "OK1") (pin "6") (pinfunction "BAS_6") (pintype "passive"))
    )
    (net (code "79") (name "unconnected-(U$1-A_AMARILLO-PadPAAMA)") (class "Default")
      (node (ref "U$1") (pin "PAAMA") (pinfunction "A_AMARILLO_PAAMA") (pintype "bidirectional"))
    )
    (net (code "80") (name "unconnected-(U$1-A_VERDE-PadPAV)") (class "Default")
      (node (ref "U$1") (pin "PAV") (pinfunction "A_VERDE_PAV") (pintype "bidirectional"))
    )
    (net (code "81") (name "unconnected-(U$1-K-AMARILLO-PadPKAM)") (class "Default")
      (node (ref "U$1") (pin "PKAM") (pinfunction "K-AMARILLO_PKAM") (pintype "bidirectional"))
    )
    (net (code "82") (name "unconnected-(U$1-K_VERDE-PadPKV)") (class "Default")
      (node (ref "U$1") (pin "PKV") (pinfunction "K_VERDE_PKV") (pintype "bidirectional"))
    )
    (net (code "83") (name "unconnected-(U$2-PadP1)") (class "Default")
      (node (ref "U$2") (pin "P1") (pinfunction "P1_P1") (pintype "bidirectional"))
    )
    (net (code "84") (name "unconnected-(U$2-PadP6)") (class "Default")
      (node (ref "U$2") (pin "P6") (pinfunction "P6_P6") (pintype "bidirectional"))
    )
    (net (code "85") (name "unconnected-(X1-Pad1)") (class "Default")
      (node (ref "X1") (pin "1") (pinfunction "1_1") (pintype "passive"))
    )
    (net (code "86") (name "unconnected-(X1-Pad4)") (class "Default")
      (node (ref "X1") (pin "4") (pinfunction "4_4") (pintype "passive"))
    )
    (net (code "87") (name "unconnected-(X1-Pad6)") (class "Default")
      (node (ref "X1") (pin "6") (pinfunction "6_6") (pintype "passive"))
    )
    (net (code "88") (name "unconnected-(X1-Pad7)") (class "Default")
      (node (ref "X1") (pin "7") (pinfunction "7_7") (pintype "passive"))
    )
    (net (code "89") (name "unconnected-(X1-Pad8)") (class "Default")
      (node (ref "X1") (pin "8") (pinfunction "8_8") (pintype "passive"))
    )
    (net (code "90") (name "unconnected-(X1-Pad9)") (class "Default")
      (node (ref "X1") (pin "9") (pinfunction "9_9") (pintype "passive"))
    )
  )
)
